# GNSSModule.net
KiCad netlist of a schematic drawn in Altium Designer
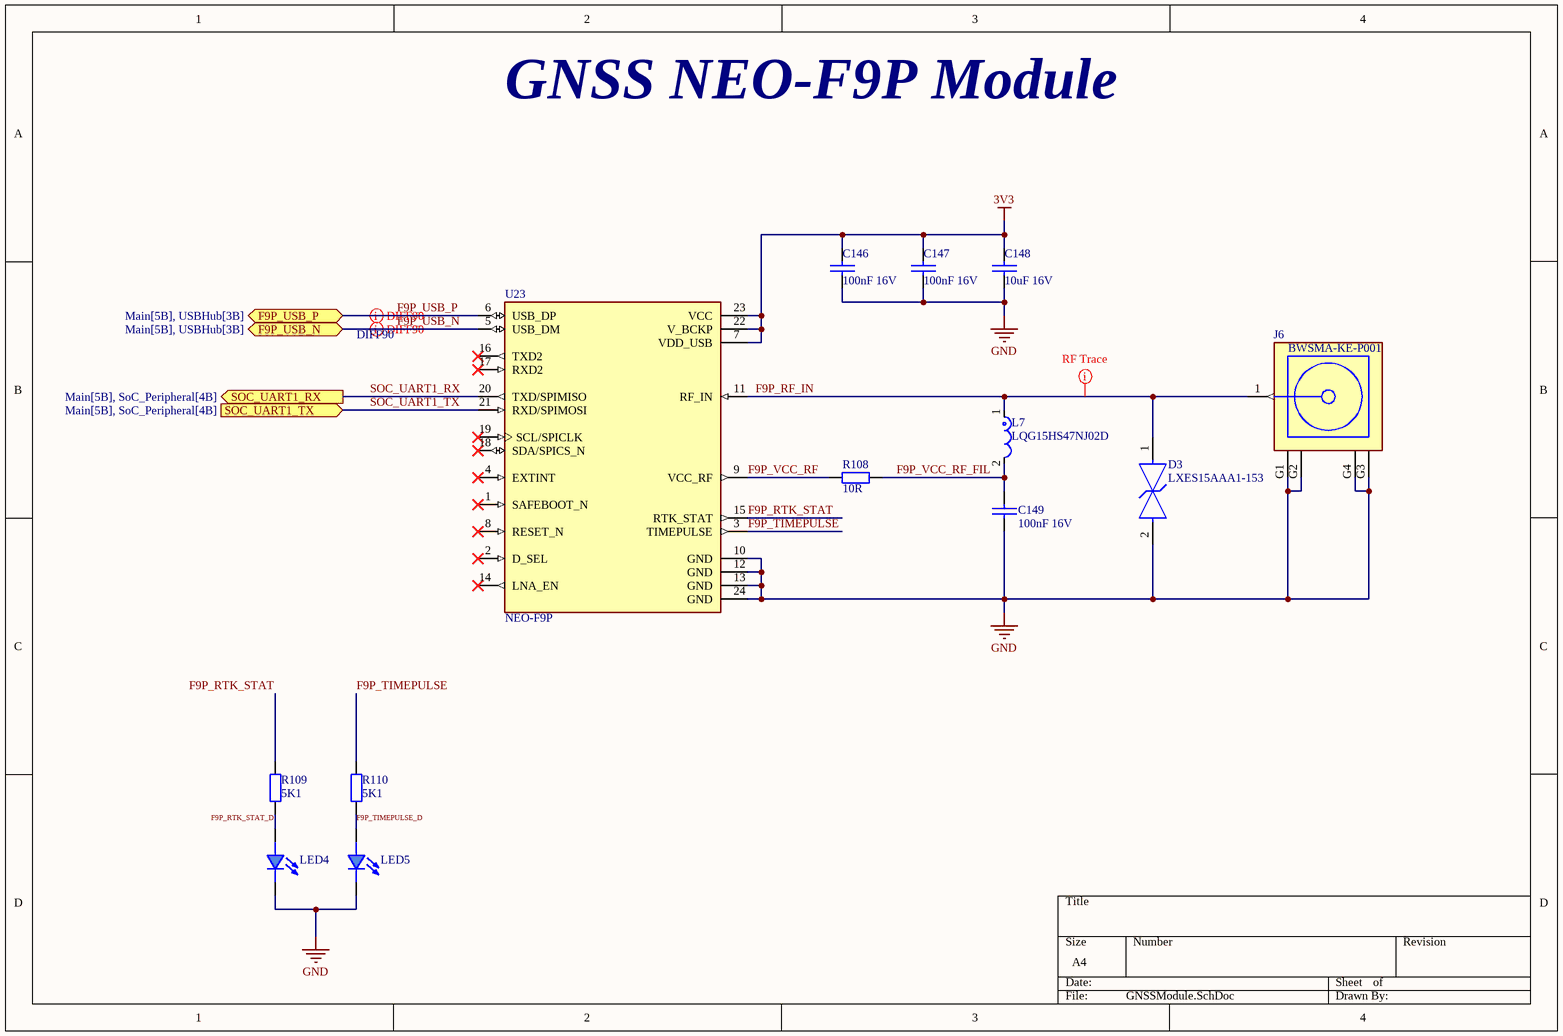
[diagram p0: GNSSModule.SchDoc]

(export (version "E")
  (design (tool "Eeschema 10.0.6"))
  (components
    (comp (ref "C146")
      (value "100nF 16V")
      (footprint "C_0402")
      (description "Capacitor 0402 SMD")
      (libsource (lib "tor1kkLib") (part "C_0402"))
    )
    (comp (ref "C147")
      (value "100nF 16V")
      (footprint "C_0402")
      (description "Capacitor 0402 SMD")
      (libsource (lib "tor1kkLib") (part "C_0402"))
    )
    (comp (ref "C148")
      (value "10uF 16V")
      (footprint "C_0603")
      (description "Capacitor 0603 SMD")
      (libsource (lib "tor1kkLib") (part "C_0603"))
    )
    (comp (ref "C149")
      (value "100nF 16V")
      (footprint "C_0402")
      (description "Capacitor 0402 SMD")
      (libsource (lib "tor1kkLib") (part "C_0402"))
    )
    (comp (ref "D3")
      (value "LXES15AAA1-153")
      (footprint "FP-LXES15-MFG")
      (description "TVS DIODE 4V 1005")
      (libsource (lib "Altium Content Vault") (part "876f4347bf90aa6f500f43e3cd03972"))
    )
    (comp (ref "J6")
      (value "BWSMA-KE-P001")
      (footprint "BATWIRELESS_BWSMA-KE-P001")
      (description "1 Inner Hole SMA Board-End Staggered pins 50Ω 5.2mm SMD Coaxial Connectors (RF) ROHS")
      (fields (field (name "MANUFACTURER") "BAT WIRELESS"))
      (libsource (lib "tor1kkLib") (part "BWSMA-KE-P001"))
    )
    (comp (ref "L7")
      (value "LQG15HS47NJ02D")
      (footprint "FP-LQG15HH_02-IPC_B")
      (description "Multilayer type RF Inductor 47nH ±5% 0.72Ω 300mA 0402")
      (fields (field (name "TOLERANCE") "5%"))
      (libsource (lib "Altium Content Vault") (part "4cc4b267dca4c8e51f7102f422741d8"))
    )
    (comp (ref "LED4")
      (value "LED_0603_BLUE")
      (footprint "LED_0603")
      (libsource (lib "tor1kkLib") (part "LED_0603_BLUE"))
    )
    (comp (ref "LED5")
      (value "LED_0603_BLUE")
      (footprint "LED_0603")
      (libsource (lib "tor1kkLib") (part "LED_0603_BLUE"))
    )
    (comp (ref "R108")
      (value "10R")
      (footprint "R_0402")
      (description "Resistor 0402 SMD")
      (libsource (lib "tor1kkLib") (part "R_0402"))
    )
    (comp (ref "R109")
      (value "5K1")
      (footprint "R_0603")
      (description "Resistor 0603 SMD")
      (libsource (lib "tor1kkLib") (part "R_0603"))
    )
    (comp (ref "R110")
      (value "5K1")
      (footprint "R_0603")
      (description "Resistor 0603 SMD")
      (libsource (lib "tor1kkLib") (part "R_0603"))
    )
    (comp (ref "U23")
      (value "NEO-F9P")
      (footprint "NEO-F9P")
      (description "RF Receiver BeiDou, Galileo, GLONASS, GNSS, GPS -167dBm 921.6kbps")
      (fields (field (name "MANUFACTURER") "u-blox") (field (name "MANUFACTURER PART NUMBER") "NEO-F9P-15B"))
      (libsource (lib "tor1kkLib") (part "NEO-F9P"))
    )
  )
  (nets
    (net (code "1") (name "/F9P_RF_IN") (class "Default")
      (node (ref "D3") (pin "1") (pinfunction "1_1") (pintype "passive"))
      (node (ref "J6") (pin "1") (pinfunction "SIG_1") (pintype "output"))
      (node (ref "L7") (pin "1") (pinfunction "1_1") (pintype "passive"))
      (node (ref "U23") (pin "11") (pinfunction "RF_IN_11") (pintype "input"))
    )
    (net (code "2") (name "/F9P_RTK_STAT") (class "Default")
      (node (ref "R109") (pin "1") (pintype "passive"))
      (node (ref "U23") (pin "15") (pinfunction "RTK_STAT_15") (pintype "output"))
    )
    (net (code "3") (name "/F9P_RTK_STAT_D") (class "Default")
      (node (ref "LED4") (pin "1") (pinfunction "A_1") (pintype "passive"))
      (node (ref "R109") (pin "2") (pintype "passive"))
    )
    (net (code "4") (name "/F9P_TIMEPULSE") (class "Default")
      (node (ref "R110") (pin "1") (pintype "passive"))
      (node (ref "U23") (pin "3") (pinfunction "TIMEPULSE_3") (pintype "output"))
    )
    (net (code "5") (name "/F9P_TIMEPULSE_D") (class "Default")
      (node (ref "LED5") (pin "1") (pinfunction "A_1") (pintype "passive"))
      (node (ref "R110") (pin "2") (pintype "passive"))
    )
    (net (code "6") (name "/F9P_USB_N") (class "Default")
      (node (ref "U23") (pin "5") (pinfunction "USB_DM_5") (pintype "bidirectional"))
    )
    (net (code "7") (name "/F9P_USB_P") (class "Default")
      (node (ref "U23") (pin "6") (pinfunction "USB_DP_6") (pintype "bidirectional"))
    )
    (net (code "8") (name "/F9P_VCC_RF") (class "Default")
      (node (ref "R108") (pin "2") (pintype "passive"))
      (node (ref "U23") (pin "9") (pinfunction "VCC_RF_9") (pintype "output"))
    )
    (net (code "9") (name "/F9P_VCC_RF_FIL") (class "Default")
      (node (ref "C149") (pin "1") (pintype "passive"))
      (node (ref "L7") (pin "2") (pinfunction "2_2") (pintype "passive"))
      (node (ref "R108") (pin "1") (pintype "passive"))
    )
    (net (code "10") (name "/SOC_UART1_RX") (class "Default")
      (node (ref "U23") (pin "20") (pinfunction "TXD/SPIMISO_20") (pintype "output"))
    )
    (net (code "11") (name "/SOC_UART1_TX") (class "Default")
      (node (ref "U23") (pin "21") (pinfunction "RXD/SPIMOSI_21") (pintype "input"))
    )
    (net (code "12") (name "3V3") (class "Default")
      (node (ref "C146") (pin "1") (pintype "passive"))
      (node (ref "C147") (pin "1") (pintype "passive"))
      (node (ref "C148") (pin "1") (pintype "passive"))
      (node (ref "U23") (pin "22") (pinfunction "V_BCKP_22") (pintype "power_in"))
      (node (ref "U23") (pin "23") (pinfunction "VCC_23") (pintype "power_in"))
      (node (ref "U23") (pin "7") (pinfunction "VDD_USB_7") (pintype "power_in"))
    )
    (net (code "13") (name "GND") (class "Default")
      (node (ref "C146") (pin "2") (pintype "passive"))
      (node (ref "C147") (pin "2") (pintype "passive"))
      (node (ref "C148") (pin "2") (pintype "passive"))
      (node (ref "C149") (pin "2") (pintype "passive"))
      (node (ref "D3") (pin "2") (pinfunction "2_2") (pintype "passive"))
      (node (ref "J6") (pin "G1") (pinfunction "GND_G1") (pintype "power_in"))
      (node (ref "J6") (pin "G2") (pinfunction "GND_G2") (pintype "power_in"))
      (node (ref "J6") (pin "G3") (pinfunction "GND_G3") (pintype "power_in"))
      (node (ref "J6") (pin "G4") (pinfunction "GND_G4") (pintype "power_in"))
      (node (ref "LED4") (pin "2") (pinfunction "C_2") (pintype "passive"))
      (node (ref "LED5") (pin "2") (pinfunction "C_2") (pintype "passive"))
      (node (ref "U23") (pin "10") (pinfunction "GND_10") (pintype "power_in"))
      (node (ref "U23") (pin "12") (pinfunction "GND_12") (pintype "power_in"))
      (node (ref "U23") (pin "13") (pinfunction "GND_13") (pintype "power_in"))
      (node (ref "U23") (pin "24") (pinfunction "GND_24") (pintype "power_in"))
    )
    (net (code "14") (name "unconnected-(U23-D_SEL-Pad2)") (class "Default")
      (node (ref "U23") (pin "2") (pinfunction "D_SEL_2") (pintype "input+no_connect"))
    )
    (net (code "15") (name "unconnected-(U23-EXTINT-Pad4)") (class "Default")
      (node (ref "U23") (pin "4") (pinfunction "EXTINT_4") (pintype "input+no_connect"))
    )
    (net (code "16") (name "unconnected-(U23-LNA_EN-Pad14)") (class "Default")
      (node (ref "U23") (pin "14") (pinfunction "LNA_EN_14") (pintype "output+no_connect"))
    )
    (net (code "17") (name "unconnected-(U23-RESET_N-Pad8)") (class "Default")
      (node (ref "U23") (pin "8") (pinfunction "RESET_N_8") (pintype "input+no_connect"))
    )
    (net (code "18") (name "unconnected-(U23-RXD2-Pad17)") (class "Default")
      (node (ref "U23") (pin "17") (pinfunction "RXD2_17") (pintype "input+no_connect"))
    )
    (net (code "19") (name "unconnected-(U23-SAFEBOOT_N-Pad1)") (class "Default")
      (node (ref "U23") (pin "1") (pinfunction "SAFEBOOT_N_1") (pintype "input+no_connect"))
    )
    (net (code "20") (name "unconnected-(U23-SCL{slash}SPICLK-Pad19)") (class "Default")
      (node (ref "U23") (pin "19") (pinfunction "SCL/SPICLK_19") (pintype "input+no_connect"))
    )
    (net (code "21") (name "unconnected-(U23-SDA{slash}SPICS_N-Pad18)") (class "Default")
      (node (ref "U23") (pin "18") (pinfunction "SDA/SPICS_N_18") (pintype "bidirectional+no_connect"))
    )
    (net (code "22") (name "unconnected-(U23-TXD2-Pad16)") (class "Default")
      (node (ref "U23") (pin "16") (pinfunction "TXD2_16") (pintype "output+no_connect"))
    )
  )
)
